# Enc28j60.net
KiCad netlist of a schematic drawn in Altium Designer
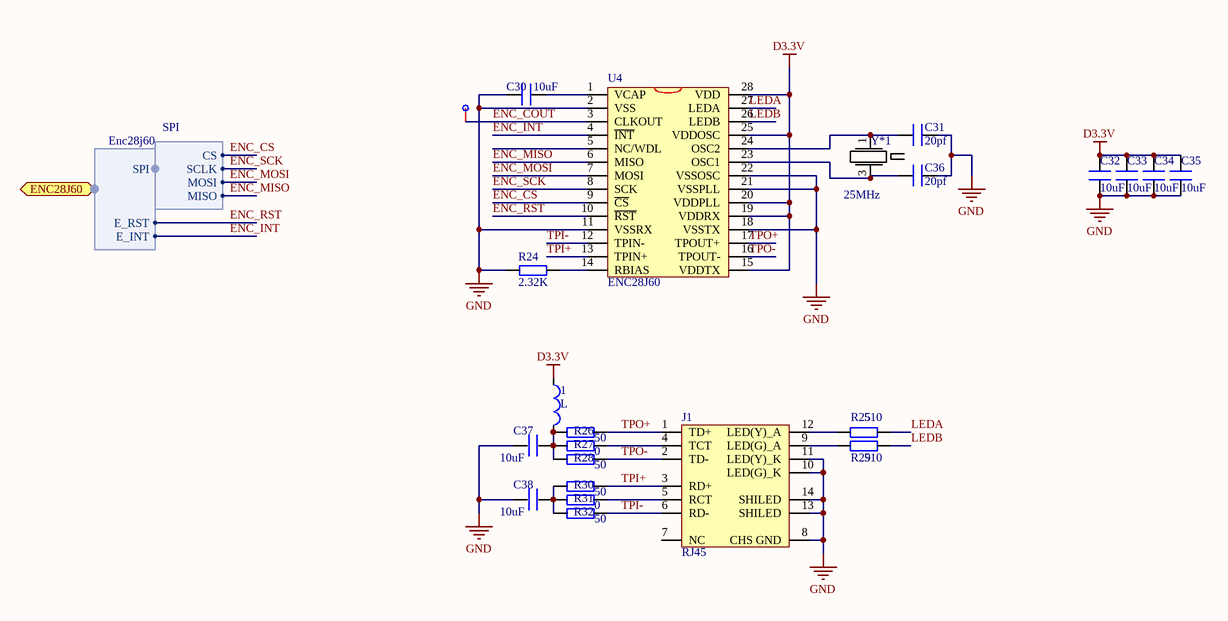
[diagram p0: Enc28j60.SchDoc]

(export (version "E")
  (design (tool "Eeschema 10.0.6"))
  (components
    (comp (ref "*2") (value "Point") (footprint "Point") (libsource (lib "authuir") (part "Point")))
    (comp (ref "1") (value "L") (footprint "0805") (libsource (lib "authuir") (part "L")))
    (comp (ref "C30") (value "10uF") (footprint "0805") (libsource (lib "ENC28J60网络模块封装库") (part "C")))
    (comp (ref "C31") (value "20pf") (footprint "0603P") (libsource (lib "ENC28J60网络模块_SCH") (part "C")))
    (comp (ref "C32") (value "10uF") (footprint "0603P") (libsource (lib "ENC28J60网络模块封装库") (part "C")))
    (comp (ref "C33") (value "10uF") (footprint "0603P") (libsource (lib "ENC28J60网络模块封装库") (part "C")))
    (comp (ref "C34") (value "10uF") (footprint "0603P") (libsource (lib "ENC28J60网络模块封装库") (part "C")))
    (comp (ref "C35") (value "10uF") (footprint "0603P") (libsource (lib "ENC28J60网络模块封装库") (part "C")))
    (comp (ref "C36") (value "20pf") (footprint "0603P") (libsource (lib "ENC28J60网络模块_SCH") (part "C")))
    (comp (ref "C37") (value "10uF") (footprint "0603P") (libsource (lib "ENC28J60网络模块封装库") (part "C")))
    (comp (ref "C38") (value "10uF") (footprint "0603P") (libsource (lib "ENC28J60网络模块封装库") (part "C")))
    (comp (ref "J1")
      (value "RJ45")
      (footprint "HR911105A")
      (libsource (lib "ENC28J60网络模块封装库") (part "HR911105"))
    )
    (comp (ref "R24") (value "2.32K") (footprint "0603P") (libsource (lib "ENC28J60网络模块封装库") (part "R")))
    (comp (ref "R25") (value "510") (footprint "0603P") (libsource (lib "ENC28J60网络模块封装库") (part "R")))
    (comp (ref "R26") (value "50") (footprint "0603P") (libsource (lib "ENC28J60网络模块封装库") (part "R")))
    (comp (ref "R27") (value "0") (footprint "0603P") (libsource (lib "ENC28J60网络模块封装库") (part "R")))
    (comp (ref "R28") (value "50") (footprint "0603P") (libsource (lib "ENC28J60网络模块封装库") (part "R")))
    (comp (ref "R29") (value "510") (footprint "0603P") (libsource (lib "ENC28J60网络模块封装库") (part "R")))
    (comp (ref "R30") (value "50") (footprint "0603P") (libsource (lib "ENC28J60网络模块封装库") (part "R")))
    (comp (ref "R31") (value "0") (footprint "0603P") (libsource (lib "ENC28J60网络模块封装库") (part "R")))
    (comp (ref "R32") (value "50") (footprint "0603P") (libsource (lib "ENC28J60网络模块封装库") (part "R")))
    (comp (ref "U4")
      (value "ENC28J60")
      (footprint "SSOP28")
      (libsource (lib "ENC28J60网络模块_SCH") (part "ENC28J60"))
    )
    (comp (ref "Y*1") (value "25MHz") (footprint "4脚晶振") (libsource (lib "authuir") (part "XTAL_16M")))
  )
  (nets
    (net (code "2") (name "/ENC_COUT") (class "Default")
      (node (ref "*2") (pin "1") (pinfunction "Point_1") (pintype "passive"))
      (node (ref "U4") (pin "3") (pinfunction "CLKOUT_3") (pintype "passive"))
    )
    (net (code "3") (name "/ENC_CS") (class "Default")
      (node (ref "U4") (pin "9") (pinfunction "~{CS}_9") (pintype "passive"))
    )
    (net (code "4") (name "/ENC_INT") (class "Default")
      (node (ref "U4") (pin "4") (pinfunction "~{INT}_4") (pintype "passive"))
    )
    (net (code "5") (name "/ENC_MISO") (class "Default")
      (node (ref "U4") (pin "6") (pinfunction "MISO_6") (pintype "passive"))
    )
    (net (code "6") (name "/ENC_MOSI") (class "Default")
      (node (ref "U4") (pin "7") (pinfunction "MOSI_7") (pintype "passive"))
    )
    (net (code "7") (name "/ENC_RST") (class "Default")
      (node (ref "U4") (pin "10") (pinfunction "~{RST}_10") (pintype "passive"))
    )
    (net (code "8") (name "/ENC_SCK") (class "Default")
      (node (ref "U4") (pin "8") (pinfunction "SCK_8") (pintype "passive"))
    )
    (net (code "9") (name "/LEDA") (class "Default")
      (node (ref "R25") (pin "2") (pintype "passive"))
      (node (ref "U4") (pin "27") (pinfunction "LEDA_27") (pintype "passive"))
    )
    (net (code "10") (name "/LEDB") (class "Default")
      (node (ref "R29") (pin "2") (pintype "passive"))
      (node (ref "U4") (pin "26") (pinfunction "LEDB_26") (pintype "passive"))
    )
    (net (code "11") (name "/TPI+") (class "Default")
      (node (ref "J1") (pin "3") (pinfunction "RD+_3") (pintype "passive"))
      (node (ref "R30") (pin "2") (pintype "passive"))
      (node (ref "U4") (pin "13") (pinfunction "TPIN+_13") (pintype "passive"))
    )
    (net (code "12") (name "/TPI-") (class "Default")
      (node (ref "J1") (pin "6") (pinfunction "RD-_6") (pintype "passive"))
      (node (ref "R32") (pin "2") (pintype "passive"))
      (node (ref "U4") (pin "12") (pinfunction "TPIN-_12") (pintype "passive"))
    )
    (net (code "13") (name "/TPO+") (class "Default")
      (node (ref "J1") (pin "1") (pinfunction "TD+_1") (pintype "passive"))
      (node (ref "R26") (pin "2") (pintype "passive"))
      (node (ref "U4") (pin "17") (pinfunction "TPOUT+_17") (pintype "passive"))
    )
    (net (code "14") (name "/TPO-") (class "Default")
      (node (ref "J1") (pin "2") (pinfunction "TD-_2") (pintype "passive"))
      (node (ref "R28") (pin "2") (pintype "passive"))
      (node (ref "U4") (pin "16") (pinfunction "TPOUT-_16") (pintype "passive"))
    )
    (net (code "16") (name "D3.3V") (class "Default")
      (node (ref "1") (pin "2") (pinfunction "2_2") (pintype "passive"))
      (node (ref "C32") (pin "2") (pintype "passive"))
      (node (ref "C33") (pin "2") (pintype "passive"))
      (node (ref "C34") (pin "2") (pintype "passive"))
      (node (ref "C35") (pin "2") (pintype "passive"))
      (node (ref "U4") (pin "15") (pinfunction "VDDTX_15") (pintype "passive"))
      (node (ref "U4") (pin "19") (pinfunction "VDDRX_19") (pintype "passive"))
      (node (ref "U4") (pin "20") (pinfunction "VDDPLL_20") (pintype "passive"))
      (node (ref "U4") (pin "25") (pinfunction "VDDOSC_25") (pintype "passive"))
      (node (ref "U4") (pin "28") (pinfunction "VDD_28") (pintype "passive"))
    )
    (net (code "17") (name "GND") (class "Default")
      (node (ref "C30") (pin "1") (pintype "passive"))
      (node (ref "C31") (pin "2") (pintype "passive"))
      (node (ref "C32") (pin "1") (pintype "passive"))
      (node (ref "C33") (pin "1") (pintype "passive"))
      (node (ref "C34") (pin "1") (pintype "passive"))
      (node (ref "C35") (pin "1") (pintype "passive"))
      (node (ref "C36") (pin "2") (pintype "passive"))
      (node (ref "C37") (pin "1") (pintype "passive"))
      (node (ref "C38") (pin "1") (pintype "passive"))
      (node (ref "J1") (pin "10") (pinfunction "LED(G)_K_10") (pintype "passive"))
      (node (ref "J1") (pin "11") (pinfunction "LED(Y)_K_11") (pintype "passive"))
      (node (ref "J1") (pin "13") (pinfunction "SHILED_13") (pintype "passive"))
      (node (ref "J1") (pin "14") (pinfunction "SHILED_14") (pintype "passive"))
      (node (ref "J1") (pin "8") (pinfunction "CHS_GND_8") (pintype "passive"))
      (node (ref "R24") (pin "1") (pintype "passive"))
      (node (ref "U4") (pin "11") (pinfunction "VSSRX_11") (pintype "passive"))
      (node (ref "U4") (pin "18") (pinfunction "VSSTX_18") (pintype "passive"))
      (node (ref "U4") (pin "2") (pinfunction "VSS_2") (pintype "passive"))
      (node (ref "U4") (pin "21") (pinfunction "VSSPLL_21") (pintype "passive"))
      (node (ref "U4") (pin "22") (pinfunction "VSSOSC_22") (pintype "passive"))
    )
    (net (code "18") (name "Net-(1-Pad1)") (class "Default")
      (node (ref "1") (pin "1") (pinfunction "1_1") (pintype "passive"))
      (node (ref "C37") (pin "2") (pintype "passive"))
      (node (ref "R26") (pin "1") (pintype "passive"))
      (node (ref "R27") (pin "1") (pintype "passive"))
      (node (ref "R28") (pin "1") (pintype "passive"))
    )
    (net (code "19") (name "Net-(C38-Pad2)") (class "Default")
      (node (ref "C38") (pin "2") (pintype "passive"))
      (node (ref "R30") (pin "1") (pintype "passive"))
      (node (ref "R31") (pin "1") (pintype "passive"))
      (node (ref "R32") (pin "1") (pintype "passive"))
    )
    (net (code "20") (name "Net-(J1-LED(G)_A)") (class "Default")
      (node (ref "J1") (pin "9") (pinfunction "LED(G)_A_9") (pintype "passive"))
      (node (ref "R29") (pin "1") (pintype "passive"))
    )
    (net (code "21") (name "Net-(J1-LED(Y)_A)") (class "Default")
      (node (ref "J1") (pin "12") (pinfunction "LED(Y)_A_12") (pintype "passive"))
      (node (ref "R25") (pin "1") (pintype "passive"))
    )
    (net (code "22") (name "Net-(J1-RCT)") (class "Default")
      (node (ref "J1") (pin "5") (pinfunction "RCT_5") (pintype "passive"))
      (node (ref "R31") (pin "2") (pintype "passive"))
    )
    (net (code "23") (name "Net-(J1-TCT)") (class "Default")
      (node (ref "J1") (pin "4") (pinfunction "TCT_4") (pintype "passive"))
      (node (ref "R27") (pin "2") (pintype "passive"))
    )
    (net (code "24") (name "Net-(U4-OSC1)") (class "Default")
      (node (ref "C36") (pin "1") (pintype "passive"))
      (node (ref "U4") (pin "23") (pinfunction "OSC1_23") (pintype "passive"))
      (node (ref "Y*1") (pin "3") (pinfunction "O_3") (pintype "passive"))
    )
    (net (code "25") (name "Net-(U4-OSC2)") (class "Default")
      (node (ref "C31") (pin "1") (pintype "passive"))
      (node (ref "U4") (pin "24") (pinfunction "OSC2_24") (pintype "passive"))
      (node (ref "Y*1") (pin "1") (pinfunction "O_1") (pintype "passive"))
    )
    (net (code "26") (name "Net-(U4-RBIAS)") (class "Default")
      (node (ref "R24") (pin "2") (pintype "passive"))
      (node (ref "U4") (pin "14") (pinfunction "RBIAS_14") (pintype "passive"))
    )
    (net (code "27") (name "Net-(U4-VCAP)") (class "Default")
      (node (ref "C30") (pin "2") (pintype "passive"))
      (node (ref "U4") (pin "1") (pinfunction "VCAP_1") (pintype "passive"))
    )
    (net (code "28") (name "unconnected-(J1-NC-Pad7)") (class "Default")
      (node (ref "J1") (pin "7") (pinfunction "NC_7") (pintype "passive"))
    )
    (net (code "29") (name "unconnected-(U4-NC{slash}WDL-Pad5)") (class "Default")
      (node (ref "U4") (pin "5") (pinfunction "NC/WDL_5") (pintype "passive"))
    )
    (net (code "30") (name "unconnected-(Y*1-G-Pad2)") (class "Default")
      (node (ref "Y*1") (pin "2") (pinfunction "G_2") (pintype "passive"))
    )
    (net (code "31") (name "unconnected-(Y*1-G-Pad4)") (class "Default")
      (node (ref "Y*1") (pin "4") (pinfunction "G_4") (pintype "passive"))
    )
  )
)
